# basic-schematic-usb.net
KiCad netlist of a schematic drawn in EAGLE
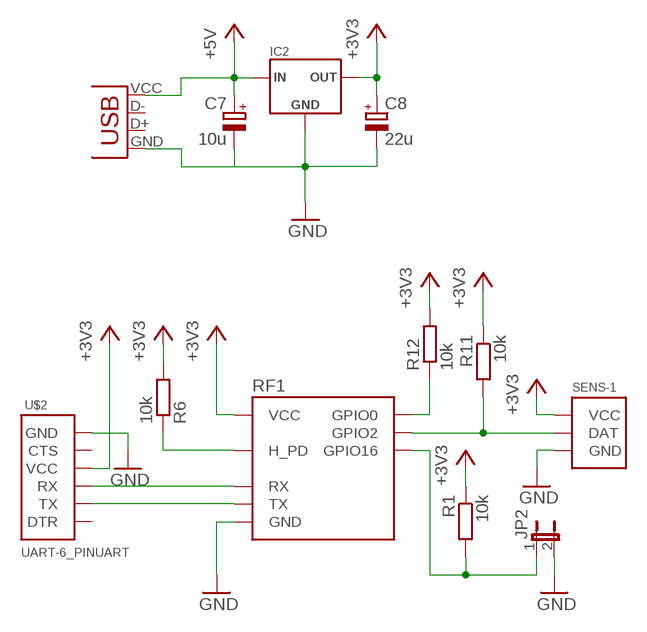
[diagram p0: schematic, sheet 1]

(export (version "E")
  (design (tool "Eeschema 10.0.6"))
  (components
    (comp (ref "C7")
      (value "10u")
      (footprint "eagle-import:E2,5-6")
      (libsource (lib "eagle-import") (part "CPOL-EUE2.5-6"))
    )
    (comp (ref "C8")
      (value "22u")
      (footprint "eagle-import:E2,5-6")
      (libsource (lib "eagle-import") (part "CPOL-EUE2.5-6"))
    )
    (comp (ref "CON1")
      (value "USB2.5-2.0-2.5")
      (footprint "eagle-import:USB-FEMALE-A")
      (libsource (lib "eagle-import") (part "USB2.5-2.0-2.5"))
    )
    (comp (ref "IC2")
      (value "REGULATOR-UA78M33TO220")
      (footprint "eagle-import:TO220V")
      (libsource (lib "eagle-import") (part "REGULATOR-UA78M33TO220"))
    )
    (comp (ref "JP2")
      (value "JP1E")
      (footprint "eagle-import:JP1")
      (libsource (lib "eagle-import") (part "JP1E"))
    )
    (comp (ref "R1")
      (value "10k")
      (footprint "eagle-import:0207_7")
      (libsource (lib "eagle-import") (part "R-EU_0207/7"))
    )
    (comp (ref "R6")
      (value "10k")
      (footprint "eagle-import:0207_7")
      (libsource (lib "eagle-import") (part "R-EU_0207/7"))
    )
    (comp (ref "R11")
      (value "10k")
      (footprint "eagle-import:0207_7")
      (libsource (lib "eagle-import") (part "R-EU_0207/7"))
    )
    (comp (ref "R12")
      (value "10k")
      (footprint "eagle-import:0207_7")
      (libsource (lib "eagle-import") (part "R-EU_0207/7"))
    )
    (comp (ref "RF1")
      (value "ESP2866-ESP-01THT")
      (footprint "eagle-import:ESP8266-ESP-01")
      (libsource (lib "eagle-import") (part "ESP2866-ESP-01THT"))
    )
    (comp (ref "SENS-1")
      (value "DHT11DHT11")
      (footprint "eagle-import:SENSOR-DHT11")
      (libsource (lib "eagle-import") (part "DHT11DHT11"))
    )
    (comp (ref "U$2")
      (value "UART-6_PINUART")
      (footprint "eagle-import:ANGLE-1X6")
      (libsource (lib "eagle-import") (part "UART-6_PINUART"))
    )
  )
  (nets
    (net (code "1") (name "+3V3") (class "Default")
      (node (ref "C8") (pin "+") (pinfunction "+_+") (pintype "passive"))
      (node (ref "IC2") (pin "3") (pinfunction "OUT_3") (pintype "bidirectional"))
      (node (ref "R1") (pin "1") (pinfunction "1_1") (pintype "passive"))
      (node (ref "R11") (pin "1") (pinfunction "1_1") (pintype "passive"))
      (node (ref "R12") (pin "2") (pinfunction "2_2") (pintype "passive"))
      (node (ref "R6") (pin "2") (pinfunction "2_2") (pintype "passive"))
      (node (ref "RF1") (pin "VCC") (pinfunction "VCC_VCC") (pintype "bidirectional"))
      (node (ref "SENS-1") (pin "P$1") (pinfunction "VCC_P$1") (pintype "bidirectional"))
      (node (ref "U$2") (pin "3") (pinfunction "VCC_3") (pintype "bidirectional"))
    )
    (net (code "2") (name "+5V") (class "Default")
      (node (ref "C7") (pin "+") (pinfunction "+_+") (pintype "passive"))
      (node (ref "CON1") (pin "VCC") (pinfunction "VBUS_VCC") (pintype "bidirectional"))
      (node (ref "IC2") (pin "1") (pinfunction "IN_1") (pintype "bidirectional"))
    )
    (net (code "3") (name "GND") (class "Default")
      (node (ref "C7") (pin "-") (pinfunction "-_-") (pintype "passive"))
      (node (ref "C8") (pin "-") (pinfunction "-_-") (pintype "passive"))
      (node (ref "CON1") (pin "GND") (pinfunction "GND_GND") (pintype "bidirectional"))
      (node (ref "IC2") (pin "2") (pinfunction "GND_2") (pintype "bidirectional"))
      (node (ref "JP2") (pin "2") (pinfunction "2_2") (pintype "passive"))
      (node (ref "RF1") (pin "GND") (pinfunction "GND_GND") (pintype "bidirectional"))
      (node (ref "SENS-1") (pin "P$4") (pinfunction "GND_P$4") (pintype "bidirectional"))
      (node (ref "U$2") (pin "1") (pinfunction "GND_1") (pintype "bidirectional"))
    )
    (net (code "4") (name "Net-(JP2-Pad1)") (class "Default")
      (node (ref "JP2") (pin "1") (pinfunction "1_1") (pintype "passive"))
      (node (ref "R1") (pin "2") (pinfunction "2_2") (pintype "passive"))
      (node (ref "RF1") (pin "GPIO16") (pinfunction "GPIO16_GPIO16") (pintype "bidirectional"))
    )
    (net (code "5") (name "Net-(R6-Pad1)") (class "Default")
      (node (ref "R6") (pin "1") (pinfunction "1_1") (pintype "passive"))
      (node (ref "RF1") (pin "H_PD") (pinfunction "H_PD_H_PD") (pintype "bidirectional"))
    )
    (net (code "6") (name "Net-(R12-Pad1)") (class "Default")
      (node (ref "R12") (pin "1") (pinfunction "1_1") (pintype "passive"))
      (node (ref "RF1") (pin "GPIO0") (pinfunction "GPIO0_GPIO0") (pintype "bidirectional"))
    )
    (net (code "7") (name "Net-(SENS-1-DAT)") (class "Default")
      (node (ref "R11") (pin "2") (pinfunction "2_2") (pintype "passive"))
      (node (ref "RF1") (pin "GPIO2") (pinfunction "GPIO2_GPIO2") (pintype "bidirectional"))
      (node (ref "SENS-1") (pin "P$2") (pinfunction "DAT_P$2") (pintype "bidirectional"))
    )
    (net (code "8") (name "Net-(U$2-RX)") (class "Default")
      (node (ref "RF1") (pin "RX") (pinfunction "RX_RX") (pintype "bidirectional"))
      (node (ref "U$2") (pin "4") (pinfunction "RX_4") (pintype "bidirectional"))
    )
    (net (code "9") (name "Net-(U$2-TX)") (class "Default")
      (node (ref "RF1") (pin "TX") (pinfunction "TX_TX") (pintype "bidirectional"))
      (node (ref "U$2") (pin "5") (pinfunction "TX_5") (pintype "bidirectional"))
    )
    (net (code "10") (name "unconnected-(CON1-PadD+)") (class "Default")
      (node (ref "CON1") (pin "D+") (pinfunction "D+_D+") (pintype "bidirectional"))
    )
    (net (code "11") (name "unconnected-(CON1-PadD-)") (class "Default")
      (node (ref "CON1") (pin "D-") (pinfunction "D-_D-") (pintype "bidirectional"))
    )
    (net (code "12") (name "unconnected-(U$2-CTS-Pad2)") (class "Default")
      (node (ref "U$2") (pin "2") (pinfunction "CTS_2") (pintype "bidirectional"))
    )
    (net (code "13") (name "unconnected-(U$2-DTR-Pad6)") (class "Default")
      (node (ref "U$2") (pin "6") (pinfunction "DTR_6") (pintype "bidirectional"))
    )
  )
)
